# SCH_Sensor-Rudder_Altium.net
KiCad netlist of a schematic drawn in Altium Designer
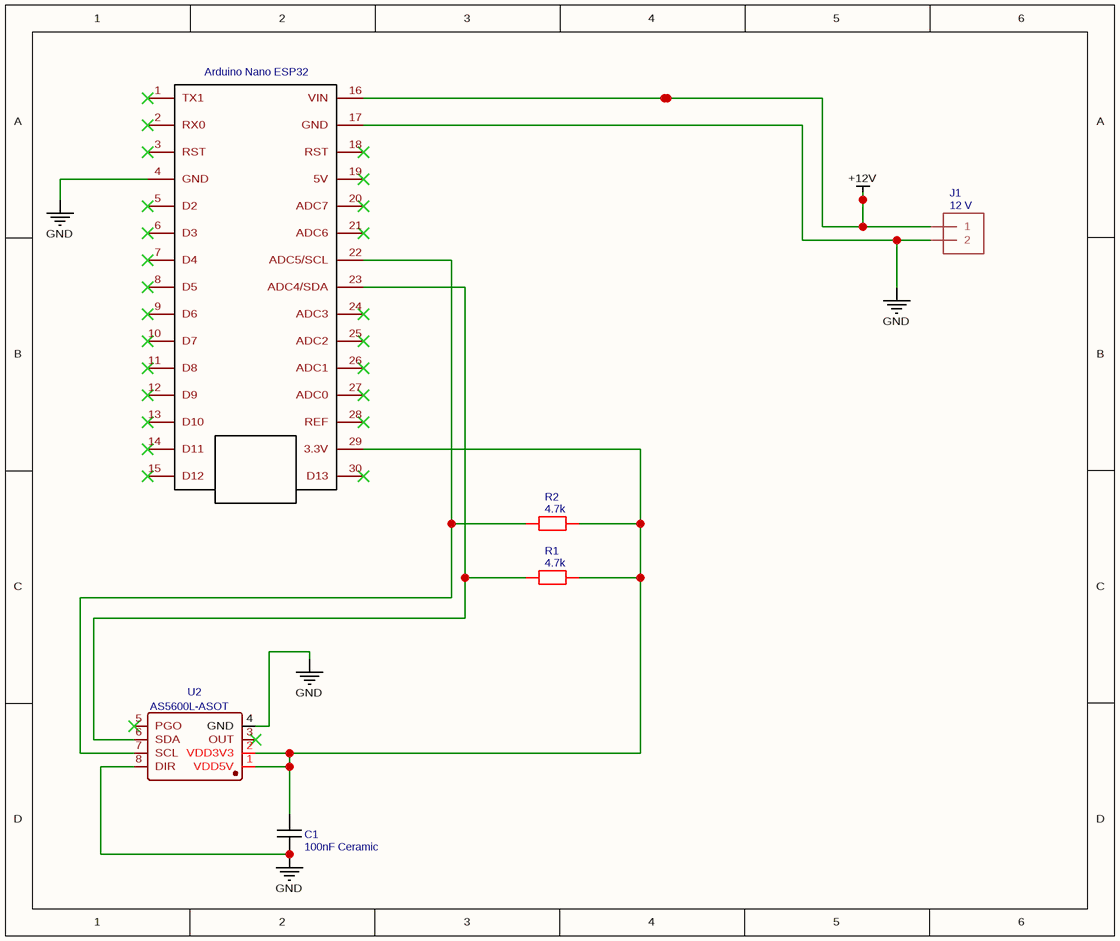
[diagram p0: SCH_Sensor-Rudder_Altium.schdoc]

(export (version "E")
  (design (tool "Eeschema 10.0.6"))
  (components
    (comp (ref "C1")
      (value "100nF Ceramic")
      (fields
        (field (name "MANUFACTURER PART") "Capacitor_Ceramic")
        (field (name "CONTRIBUTOR") "huuvinhz755")
      )
      (libsource (lib "altium-import") (part "root_3_100nF Ceramic_"))
    )
    (comp (ref "J1")
      (value "12 V")
      (fields (field (name "CONTRIBUTOR") "Adafruit"))
      (libsource (lib "altium-import") (part "root_0_12 V_"))
    )
    (comp (ref "R1")
      (value "4.7k")
      (fields (field (name "CONTRIBUTOR") "Kagutsuchi"))
      (libsource (lib "altium-import") (part "root_0_4.7k_"))
    )
    (comp (ref "R2")
      (value "4.7k")
      (fields (field (name "CONTRIBUTOR") "Kagutsuchi"))
      (libsource (lib "altium-import") (part "root_0_4.7k_"))
    )
    (comp (ref "U1")
      (value "Arduino Nano ESP32")
      (fields (field (name "CONTRIBUTOR") "Nikolay Yanev"))
      (libsource (lib "altium-import") (part "root_0_Arduino Nano ESP32_"))
    )
    (comp (ref "U2")
      (value "AS5600L-ASOT")
      (fields (field (name "MANUFACTURER") "美国AMS") (field (name "CONTRIBUTOR") "mromanini"))
      (libsource (lib "altium-import") (part "root_0_AS5600L-ASOT_"))
    )
  )
  (nets
    (net (code "1") (name "+12V") (class "Default")
      (node (ref "J1") (pin "1") (pinfunction "1_1") (pintype "passive"))
      (node (ref "U1") (pin "16") (pinfunction "VIN_16") (pintype "passive"))
    )
    (net (code "2") (name "GND") (class "Default")
      (node (ref "C1") (pin "2") (pinfunction "2_2") (pintype "passive"))
      (node (ref "J1") (pin "2") (pinfunction "2_2") (pintype "passive"))
      (node (ref "U1") (pin "17") (pinfunction "GND_17") (pintype "passive"))
      (node (ref "U1") (pin "4") (pinfunction "GND_4") (pintype "passive"))
      (node (ref "U2") (pin "4") (pinfunction "GND_4") (pintype "passive"))
      (node (ref "U2") (pin "8") (pinfunction "DIR_8") (pintype "passive"))
    )
    (net (code "3") (name "Net-(R1-1)") (class "Default")
      (node (ref "C1") (pin "1") (pinfunction "1_1") (pintype "passive"))
      (node (ref "R1") (pin "2") (pinfunction "1_2") (pintype "passive"))
      (node (ref "R2") (pin "2") (pinfunction "1_2") (pintype "passive"))
      (node (ref "U1") (pin "29") (pinfunction "3.3V_29") (pintype "passive"))
      (node (ref "U2") (pin "1") (pinfunction "VDD5V_1") (pintype "passive"))
      (node (ref "U2") (pin "2") (pinfunction "VDD3V3_2") (pintype "passive"))
    )
    (net (code "4") (name "Net-(R1-2)") (class "Default")
      (node (ref "R1") (pin "1") (pinfunction "2_1") (pintype "passive"))
      (node (ref "U1") (pin "23") (pinfunction "ADC4/SDA_23") (pintype "passive"))
      (node (ref "U2") (pin "6") (pinfunction "SDA_6") (pintype "passive"))
    )
    (net (code "5") (name "Net-(R2-2)") (class "Default")
      (node (ref "R2") (pin "1") (pinfunction "2_1") (pintype "passive"))
      (node (ref "U1") (pin "22") (pinfunction "ADC5/SCL_22") (pintype "passive"))
      (node (ref "U2") (pin "7") (pinfunction "SCL_7") (pintype "passive"))
    )
    (net (code "6") (name "unconnected-(U1-5V-Pad19)") (class "Default")
      (node (ref "U1") (pin "19") (pinfunction "5V_19") (pintype "passive+no_connect"))
    )
    (net (code "7") (name "unconnected-(U1-ADC0-Pad27)") (class "Default")
      (node (ref "U1") (pin "27") (pinfunction "ADC0_27") (pintype "passive+no_connect"))
    )
    (net (code "8") (name "unconnected-(U1-ADC1-Pad26)") (class "Default")
      (node (ref "U1") (pin "26") (pinfunction "ADC1_26") (pintype "passive+no_connect"))
    )
    (net (code "9") (name "unconnected-(U1-ADC2-Pad25)") (class "Default")
      (node (ref "U1") (pin "25") (pinfunction "ADC2_25") (pintype "passive+no_connect"))
    )
    (net (code "10") (name "unconnected-(U1-ADC3-Pad24)") (class "Default")
      (node (ref "U1") (pin "24") (pinfunction "ADC3_24") (pintype "passive+no_connect"))
    )
    (net (code "11") (name "unconnected-(U1-ADC6-Pad21)") (class "Default")
      (node (ref "U1") (pin "21") (pinfunction "ADC6_21") (pintype "passive+no_connect"))
    )
    (net (code "12") (name "unconnected-(U1-ADC7-Pad20)") (class "Default")
      (node (ref "U1") (pin "20") (pinfunction "ADC7_20") (pintype "passive+no_connect"))
    )
    (net (code "13") (name "unconnected-(U1-D2-Pad5)") (class "Default")
      (node (ref "U1") (pin "5") (pinfunction "D2_5") (pintype "passive+no_connect"))
    )
    (net (code "14") (name "unconnected-(U1-D3-Pad6)") (class "Default")
      (node (ref "U1") (pin "6") (pinfunction "D3_6") (pintype "passive+no_connect"))
    )
    (net (code "15") (name "unconnected-(U1-D4-Pad7)") (class "Default")
      (node (ref "U1") (pin "7") (pinfunction "D4_7") (pintype "passive+no_connect"))
    )
    (net (code "16") (name "unconnected-(U1-D5-Pad8)") (class "Default")
      (node (ref "U1") (pin "8") (pinfunction "D5_8") (pintype "passive+no_connect"))
    )
    (net (code "17") (name "unconnected-(U1-D6-Pad9)") (class "Default")
      (node (ref "U1") (pin "9") (pinfunction "D6_9") (pintype "passive+no_connect"))
    )
    (net (code "18") (name "unconnected-(U1-D7-Pad10)") (class "Default")
      (node (ref "U1") (pin "10") (pinfunction "D7_10") (pintype "passive+no_connect"))
    )
    (net (code "19") (name "unconnected-(U1-D8-Pad11)") (class "Default")
      (node (ref "U1") (pin "11") (pinfunction "D8_11") (pintype "passive+no_connect"))
    )
    (net (code "20") (name "unconnected-(U1-D9-Pad12)") (class "Default")
      (node (ref "U1") (pin "12") (pinfunction "D9_12") (pintype "passive+no_connect"))
    )
    (net (code "21") (name "unconnected-(U1-D10-Pad13)") (class "Default")
      (node (ref "U1") (pin "13") (pinfunction "D10_13") (pintype "passive+no_connect"))
    )
    (net (code "22") (name "unconnected-(U1-D11-Pad14)") (class "Default")
      (node (ref "U1") (pin "14") (pinfunction "D11_14") (pintype "passive+no_connect"))
    )
    (net (code "23") (name "unconnected-(U1-D12-Pad15)") (class "Default")
      (node (ref "U1") (pin "15") (pinfunction "D12_15") (pintype "passive+no_connect"))
    )
    (net (code "24") (name "unconnected-(U1-D13-Pad30)") (class "Default")
      (node (ref "U1") (pin "30") (pinfunction "D13_30") (pintype "passive+no_connect"))
    )
    (net (code "25") (name "unconnected-(U1-REF-Pad28)") (class "Default")
      (node (ref "U1") (pin "28") (pinfunction "REF_28") (pintype "passive+no_connect"))
    )
    (net (code "26") (name "unconnected-(U1-RST-Pad3)") (class "Default")
      (node (ref "U1") (pin "3") (pinfunction "RST_3") (pintype "passive+no_connect"))
    )
    (net (code "27") (name "unconnected-(U1-RST-Pad18)") (class "Default")
      (node (ref "U1") (pin "18") (pinfunction "RST_18") (pintype "passive+no_connect"))
    )
    (net (code "28") (name "unconnected-(U1-RX0-Pad2)") (class "Default")
      (node (ref "U1") (pin "2") (pinfunction "RX0_2") (pintype "passive+no_connect"))
    )
    (net (code "29") (name "unconnected-(U1-TX1-Pad1)") (class "Default")
      (node (ref "U1") (pin "1") (pinfunction "TX1_1") (pintype "passive+no_connect"))
    )
    (net (code "30") (name "unconnected-(U2-OUT-Pad3)") (class "Default")
      (node (ref "U2") (pin "3") (pinfunction "OUT_3") (pintype "passive+no_connect"))
    )
    (net (code "31") (name "unconnected-(U2-PGO-Pad5)") (class "Default")
      (node (ref "U2") (pin "5") (pinfunction "PGO_5") (pintype "passive+no_connect"))
    )
  )
)
